# Sturing_Temperatuur_Bout.net
KiCad netlist of a schematic drawn in Altium Designer
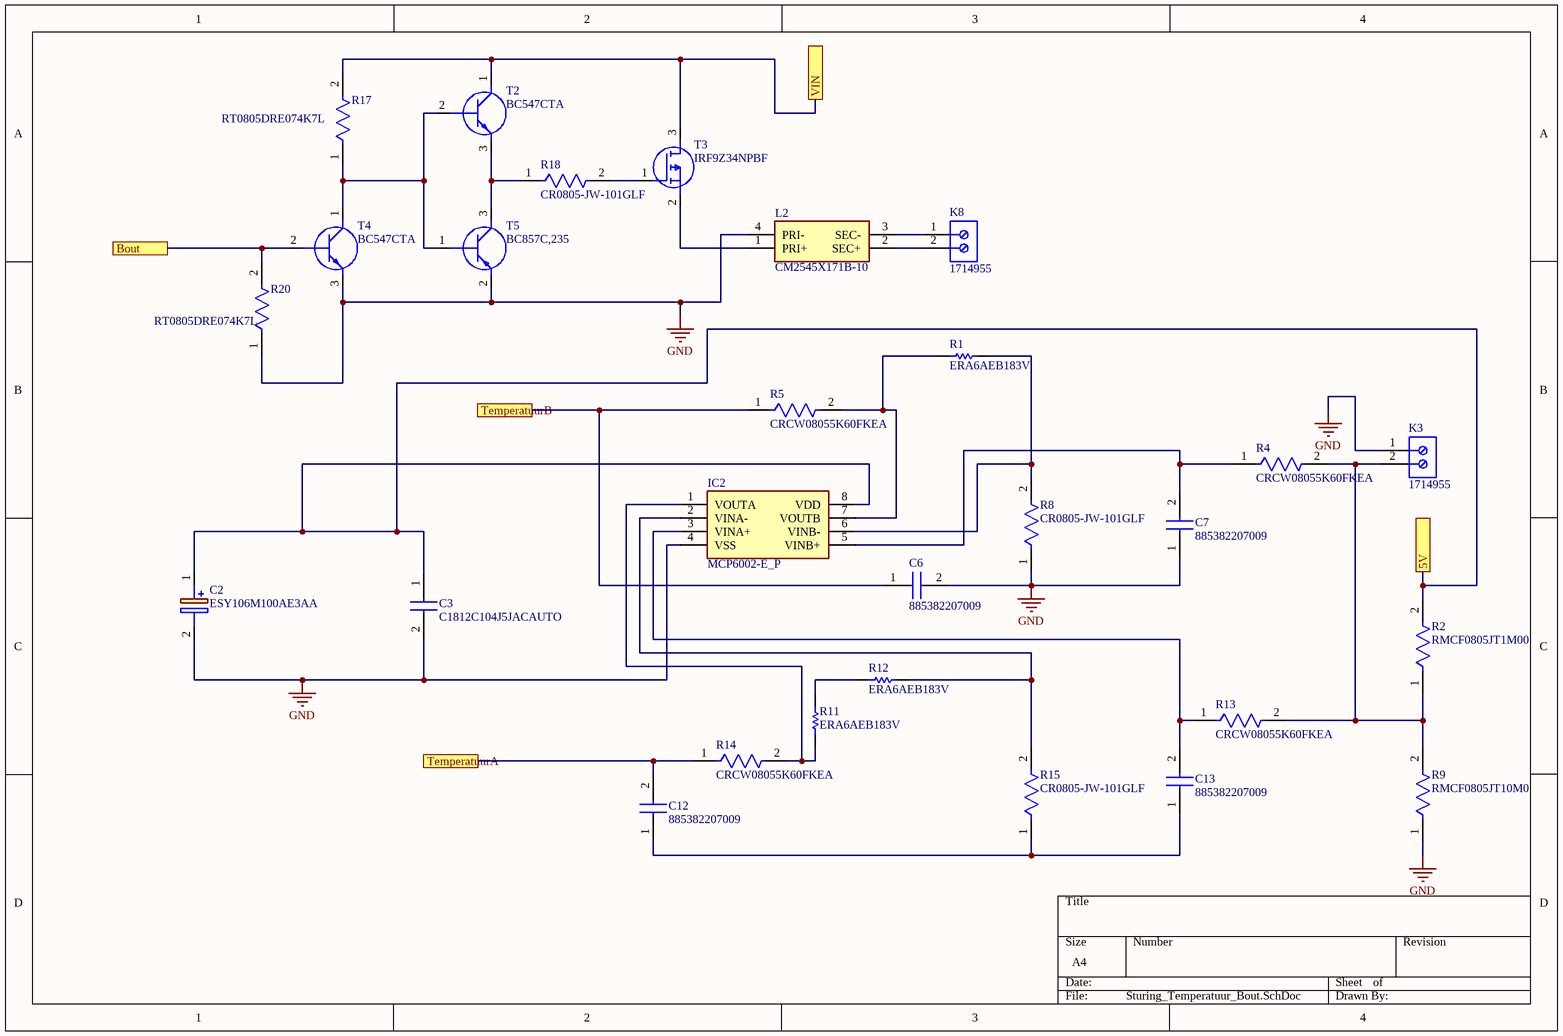
[diagram p0: Sturing_Temperatuur_Bout.SchDoc]

(export (version "E")
  (design (tool "Eeschema 10.0.6"))
  (components
    (comp (ref "C2")
      (value "ESY106M100AE3AA")
      (footprint "SamacSys:CAPPRD250W50D630H1250")
      (description "Capacitor Polarised")
      (libsource (lib "*") (part "ESY106M100AE3AA"))
    )
    (comp (ref "C3")
      (value "C1812C104J5JACAUTO")
      (footprint "SamacSys:CAPC4532X110N")
      (description "Capacitor")
      (libsource (lib "*") (part "C1812C104J5JACAUTO"))
    )
    (comp (ref "C6")
      (value "885382207009")
      (footprint "SamacSys:CAPC2012X135N")
      (description "Capacitor")
      (libsource (lib "*") (part "885382207009"))
    )
    (comp (ref "C7")
      (value "885382207009")
      (footprint "SamacSys:CAPC2012X135N")
      (description "Capacitor")
      (libsource (lib "*") (part "885382207009"))
    )
    (comp (ref "C12")
      (value "885382207009")
      (footprint "SamacSys:CAPC2012X135N")
      (description "Capacitor")
      (libsource (lib "*") (part "885382207009"))
    )
    (comp (ref "C13")
      (value "885382207009")
      (footprint "SamacSys:CAPC2012X135N")
      (description "Capacitor")
      (libsource (lib "*") (part "885382207009"))
    )
    (comp (ref "IC2")
      (value "MCP6002-E_P")
      (footprint "SamacSys:DIP781W56P254L950H533Q8N")
      (description "Integrated Circuit")
      (fields
        (field (name "MOUSER2 PART NUMBER") "579-MCP6002-E/P")
        (field (name "MANUFACTURER_PART_NUMBER") "MCP6002-E/P")
      )
      (libsource (lib "*") (part "MCP6002-E_P"))
    )
    (comp (ref "K3")
      (value "1714955")
      (footprint "PHOE-1714955_V")
      (description "PC Terminal Block, Pitch 6.35 mm, 1 x 2 Position, Height 21.5 mm, Tail Lenght 5.1 mm, RoHS, Bulk")
      (fields (field (name "MANUFACTURER") "Phoenix Contact"))
      (libsource (lib "Altium Content Vault") (part "CN-1P-F-TB2"))
    )
    (comp (ref "K8")
      (value "1714955")
      (footprint "PHOE-1714955_V")
      (description "PC Terminal Block, Pitch 6.35 mm, 1 x 2 Position, Height 21.5 mm, Tail Lenght 5.1 mm, RoHS, Bulk")
      (fields (field (name "MANUFACTURER") "Phoenix Contact"))
      (libsource (lib "Altium Content Vault") (part "CN-1P-F-TB2"))
    )
    (comp (ref "L2")
      (value "CM2545X171B-10")
      (footprint "SamacSys:CM2545X171B10")
      (description "Transformer")
      (libsource (lib "*") (part "CM2545X171B-10"))
    )
    (comp (ref "R1")
      (value "ERA6AEB183V")
      (footprint "RESC2013X60X40LL20T25")
      (fields (field (name "MANUFACTURER") "Panasonic"))
      (libsource (lib "Altium Content Vault") (part "RES"))
    )
    (comp (ref "R2")
      (value "RMCF0805JT1M00")
      (footprint "FP-RMCF0805-IPC_C")
      (description "1MΩ ±5% 0.125W 0805 Thick Film Chip Resistor AEC-Q200 compliant")
      (fields (field (name "TOLERANCE") "5%"))
      (libsource (lib "Altium Content Vault") (part "1029c3af85768c4190bb7ad29bc67b5"))
    )
    (comp (ref "R4")
      (value "CRCW08055K60FKEA")
      (footprint "FP-CRCW0805-e3-IPC_A")
      (description "RES Thick Film, 5.6kΩ, 1%, 0.125W, 100ppm/°C, 0805")
      (fields (field (name "TOLERANCE") "1%"))
      (libsource (lib "Altium Content Vault") (part "1029c3af85768c4190bb7ad29bc67b5"))
    )
    (comp (ref "R5")
      (value "CRCW08055K60FKEA")
      (footprint "FP-CRCW0805-e3-IPC_A")
      (description "RES Thick Film, 5.6kΩ, 1%, 0.125W, 100ppm/°C, 0805")
      (fields (field (name "TOLERANCE") "1%"))
      (libsource (lib "Altium Content Vault") (part "1029c3af85768c4190bb7ad29bc67b5"))
    )
    (comp (ref "R8")
      (value "CR0805-JW-101GLF")
      (footprint "FP-CR0805-IPC_A")
      (description "Thick Film Chip Resistors 0805 100Ω 0.125W 5% 200ppm/°C")
      (fields (field (name "TOLERANCE") "5%"))
      (libsource (lib "Altium Content Vault") (part "1029c3af85768c4190bb7ad29bc67b5"))
    )
    (comp (ref "R9")
      (value "RMCF0805JT10M0")
      (footprint "FP-RMCF0805-IPC_A")
      (description "10MΩ ±5% 0.125W 0805 Thick Film Chip Resistor AEC-Q200 compliant")
      (fields (field (name "TOLERANCE") "5%"))
      (libsource (lib "Altium Content Vault") (part "1029c3af85768c4190bb7ad29bc67b5"))
    )
    (comp (ref "R11")
      (value "ERA6AEB183V")
      (footprint "RESC2013X60X40LL20T25")
      (fields (field (name "MANUFACTURER") "Panasonic"))
      (libsource (lib "Altium Content Vault") (part "RES"))
    )
    (comp (ref "R12")
      (value "ERA6AEB183V")
      (footprint "RESC2013X60X40LL20T25")
      (fields (field (name "MANUFACTURER") "Panasonic"))
      (libsource (lib "Altium Content Vault") (part "RES"))
    )
    (comp (ref "R13")
      (value "CRCW08055K60FKEA")
      (footprint "FP-CRCW0805-e3-IPC_A")
      (description "RES Thick Film, 5.6kΩ, 1%, 0.125W, 100ppm/°C, 0805")
      (fields (field (name "TOLERANCE") "1%"))
      (libsource (lib "Altium Content Vault") (part "1029c3af85768c4190bb7ad29bc67b5"))
    )
    (comp (ref "R14")
      (value "CRCW08055K60FKEA")
      (footprint "FP-CRCW0805-e3-IPC_A")
      (description "RES Thick Film, 5.6kΩ, 1%, 0.125W, 100ppm/°C, 0805")
      (fields (field (name "TOLERANCE") "1%"))
      (libsource (lib "Altium Content Vault") (part "1029c3af85768c4190bb7ad29bc67b5"))
    )
    (comp (ref "R15")
      (value "CR0805-JW-101GLF")
      (footprint "FP-CR0805-IPC_A")
      (description "Thick Film Chip Resistors 0805 100Ω 0.125W 5% 200ppm/°C")
      (fields (field (name "TOLERANCE") "5%"))
      (libsource (lib "Altium Content Vault") (part "1029c3af85768c4190bb7ad29bc67b5"))
    )
    (comp (ref "R17")
      (value "RT0805DRE074K7L")
      (footprint "FP-RT0805-MFG")
      (description "RES SMD 4.7K OHM 0.5% 1/8W 0805")
      (fields
        (field (name "OCTOPART") "https://octopart.com/rt0805dre074k7l-yageo-1242027")
        (field (name "TOLERANCE") "0.01")
      )
      (libsource (lib "Altium Content Vault") (part "1029c3af85768c4190bb7ad29bc67b5"))
    )
    (comp (ref "R18")
      (value "CR0805-JW-101GLF")
      (footprint "FP-CR0805-IPC_A")
      (description "Thick Film Chip Resistors 0805 100Ω 0.125W 5% 200ppm/°C")
      (fields (field (name "TOLERANCE") "5%"))
      (libsource (lib "Altium Content Vault") (part "1029c3af85768c4190bb7ad29bc67b5"))
    )
    (comp (ref "R20")
      (value "RT0805DRE074K7L")
      (footprint "FP-RT0805-MFG")
      (description "RES SMD 4.7K OHM 0.5% 1/8W 0805")
      (fields
        (field (name "OCTOPART") "https://octopart.com/rt0805dre074k7l-yageo-1242027")
        (field (name "TOLERANCE") "0.01")
      )
      (libsource (lib "Altium Content Vault") (part "1029c3af85768c4190bb7ad29bc67b5"))
    )
    (comp (ref "T2")
      (value "BC547CTA")
      (footprint "SamacSys:MC79L15ACPG")
      (description "Transistor BJT NPN")
      (libsource (lib "*") (part "BC547CTA"))
    )
    (comp (ref "T3")
      (value "IRF9Z34NPBF")
      (footprint "SamacSys:TO254P469X1042X1967-3P")
      (description "MOSFET (P-Channel)")
      (fields (field (name "MOUSER2 PART NUMBER") "942-IRF9Z34NPBF"))
      (libsource (lib "*") (part "IRF9Z34NPBF"))
    )
    (comp (ref "T4")
      (value "BC547CTA")
      (footprint "SamacSys:MC79L15ACPG")
      (description "Transistor BJT NPN")
      (libsource (lib "*") (part "BC547CTA"))
    )
    (comp (ref "T5")
      (value "BC857C,235")
      (footprint "SamacSys:SOT95P230X110-3N")
      (description "Transistor BJT PNP")
      (fields (field (name "MOUSER2 PART NUMBER") "771-BC857C235"))
      (libsource (lib "*") (part "BC857C,235"))
    )
  )
  (nets
    (net (code "1") (name "/5V") (class "Default")
      (node (ref "C2") (pin "1") (pinfunction "+_1") (pintype "passive"))
      (node (ref "C3") (pin "1") (pinfunction "1_1") (pintype "passive"))
      (node (ref "IC2") (pin "8") (pinfunction "VDD_8") (pintype "passive"))
      (node (ref "R2") (pin "2") (pinfunction "2_2") (pintype "passive"))
    )
    (net (code "2") (name "/Bout") (class "Default")
      (node (ref "R20") (pin "2") (pinfunction "2_2") (pintype "passive"))
      (node (ref "T4") (pin "2") (pinfunction "B_2") (pintype "passive"))
    )
    (net (code "3") (name "/TemperatuurA") (class "Default")
      (node (ref "C12") (pin "2") (pinfunction "2_2") (pintype "passive"))
      (node (ref "R14") (pin "1") (pinfunction "1_1") (pintype "passive"))
    )
    (net (code "4") (name "/TemperatuurB") (class "Default")
      (node (ref "C6") (pin "1") (pinfunction "1_1") (pintype "passive"))
      (node (ref "R5") (pin "1") (pinfunction "1_1") (pintype "passive"))
    )
    (net (code "5") (name "/VIN") (class "Default")
      (node (ref "R17") (pin "2") (pinfunction "2_2") (pintype "passive"))
      (node (ref "T2") (pin "1") (pinfunction "C_1") (pintype "passive"))
      (node (ref "T3") (pin "3") (pinfunction "D_3") (pintype "passive"))
    )
    (net (code "6") (name "GND") (class "Default")
      (node (ref "C2") (pin "2") (pinfunction "-_2") (pintype "passive"))
      (node (ref "C3") (pin "2") (pinfunction "2_2") (pintype "passive"))
      (node (ref "C6") (pin "2") (pinfunction "2_2") (pintype "passive"))
      (node (ref "C7") (pin "1") (pinfunction "1_1") (pintype "passive"))
      (node (ref "IC2") (pin "4") (pinfunction "VSS_4") (pintype "passive"))
      (node (ref "K3") (pin "1") (pinfunction "1_1") (pintype "passive"))
      (node (ref "L2") (pin "4") (pinfunction "PRI-_4") (pintype "passive"))
      (node (ref "R20") (pin "1") (pinfunction "1_1") (pintype "passive"))
      (node (ref "R8") (pin "1") (pinfunction "1_1") (pintype "passive"))
      (node (ref "R9") (pin "1") (pinfunction "1_1") (pintype "passive"))
      (node (ref "T4") (pin "3") (pinfunction "E_3") (pintype "passive"))
      (node (ref "T5") (pin "2") (pinfunction "E_2") (pintype "passive"))
    )
    (net (code "7") (name "Net-(C12-Pad1)") (class "Default")
      (node (ref "C12") (pin "1") (pinfunction "1_1") (pintype "passive"))
      (node (ref "C13") (pin "1") (pinfunction "1_1") (pintype "passive"))
      (node (ref "R15") (pin "1") (pinfunction "1_1") (pintype "passive"))
    )
    (net (code "8") (name "Net-(IC2-VINA+)") (class "Default")
      (node (ref "C13") (pin "2") (pinfunction "2_2") (pintype "passive"))
      (node (ref "IC2") (pin "3") (pinfunction "VINA+_3") (pintype "passive"))
      (node (ref "R13") (pin "1") (pinfunction "1_1") (pintype "passive"))
    )
    (net (code "9") (name "Net-(IC2-VINA-)") (class "Default")
      (node (ref "IC2") (pin "2") (pinfunction "VINA-_2") (pintype "passive"))
      (node (ref "R12") (pin "2") (pinfunction "2_2") (pintype "passive"))
      (node (ref "R15") (pin "2") (pinfunction "2_2") (pintype "passive"))
    )
    (net (code "10") (name "Net-(IC2-VINB+)") (class "Default")
      (node (ref "C7") (pin "2") (pinfunction "2_2") (pintype "passive"))
      (node (ref "IC2") (pin "5") (pinfunction "VINB+_5") (pintype "passive"))
      (node (ref "R4") (pin "1") (pinfunction "1_1") (pintype "passive"))
    )
    (net (code "11") (name "Net-(IC2-VINB-)") (class "Default")
      (node (ref "IC2") (pin "6") (pinfunction "VINB-_6") (pintype "passive"))
      (node (ref "R1") (pin "2") (pinfunction "2_2") (pintype "passive"))
      (node (ref "R8") (pin "2") (pinfunction "2_2") (pintype "passive"))
    )
    (net (code "12") (name "Net-(IC2-VOUTA)") (class "Default")
      (node (ref "IC2") (pin "1") (pinfunction "VOUTA_1") (pintype "passive"))
      (node (ref "R11") (pin "1") (pinfunction "1_1") (pintype "passive"))
      (node (ref "R14") (pin "2") (pinfunction "2_2") (pintype "passive"))
    )
    (net (code "13") (name "Net-(IC2-VOUTB)") (class "Default")
      (node (ref "IC2") (pin "7") (pinfunction "VOUTB_7") (pintype "passive"))
      (node (ref "R1") (pin "1") (pinfunction "1_1") (pintype "passive"))
      (node (ref "R5") (pin "2") (pinfunction "2_2") (pintype "passive"))
    )
    (net (code "14") (name "Net-(K3-Pad2)") (class "Default")
      (node (ref "K3") (pin "2") (pinfunction "2_2") (pintype "passive"))
      (node (ref "R13") (pin "2") (pinfunction "2_2") (pintype "passive"))
      (node (ref "R2") (pin "1") (pinfunction "1_1") (pintype "passive"))
      (node (ref "R4") (pin "2") (pinfunction "2_2") (pintype "passive"))
      (node (ref "R9") (pin "2") (pinfunction "2_2") (pintype "passive"))
    )
    (net (code "15") (name "Net-(L2-PRI+)") (class "Default")
      (node (ref "L2") (pin "1") (pinfunction "PRI+_1") (pintype "passive"))
      (node (ref "T3") (pin "2") (pinfunction "S_2") (pintype "passive"))
    )
    (net (code "16") (name "Net-(L2-SEC+)") (class "Default")
      (node (ref "K8") (pin "2") (pinfunction "2_2") (pintype "passive"))
      (node (ref "L2") (pin "2") (pinfunction "SEC+_2") (pintype "passive"))
    )
    (net (code "17") (name "Net-(L2-SEC-)") (class "Default")
      (node (ref "K8") (pin "1") (pinfunction "1_1") (pintype "passive"))
      (node (ref "L2") (pin "3") (pinfunction "SEC-_3") (pintype "passive"))
    )
    (net (code "18") (name "Net-(R11-Pad2)") (class "Default")
      (node (ref "R11") (pin "2") (pinfunction "2_2") (pintype "passive"))
      (node (ref "R12") (pin "1") (pinfunction "1_1") (pintype "passive"))
    )
    (net (code "19") (name "Net-(T2-B)") (class "Default")
      (node (ref "R17") (pin "1") (pinfunction "1_1") (pintype "passive"))
      (node (ref "T2") (pin "2") (pinfunction "B_2") (pintype "passive"))
      (node (ref "T4") (pin "1") (pinfunction "C_1") (pintype "passive"))
      (node (ref "T5") (pin "1") (pinfunction "B_1") (pintype "passive"))
    )
    (net (code "20") (name "Net-(T2-E)") (class "Default")
      (node (ref "R18") (pin "1") (pinfunction "1_1") (pintype "passive"))
      (node (ref "T2") (pin "3") (pinfunction "E_3") (pintype "passive"))
      (node (ref "T5") (pin "3") (pinfunction "C_3") (pintype "passive"))
    )
    (net (code "21") (name "Net-(T3-G)") (class "Default")
      (node (ref "R18") (pin "2") (pinfunction "2_2") (pintype "passive"))
      (node (ref "T3") (pin "1") (pinfunction "G_1") (pintype "passive"))
    )
  )
)
